# PXO_1_0.net
KiCad netlist of a schematic drawn in EAGLE
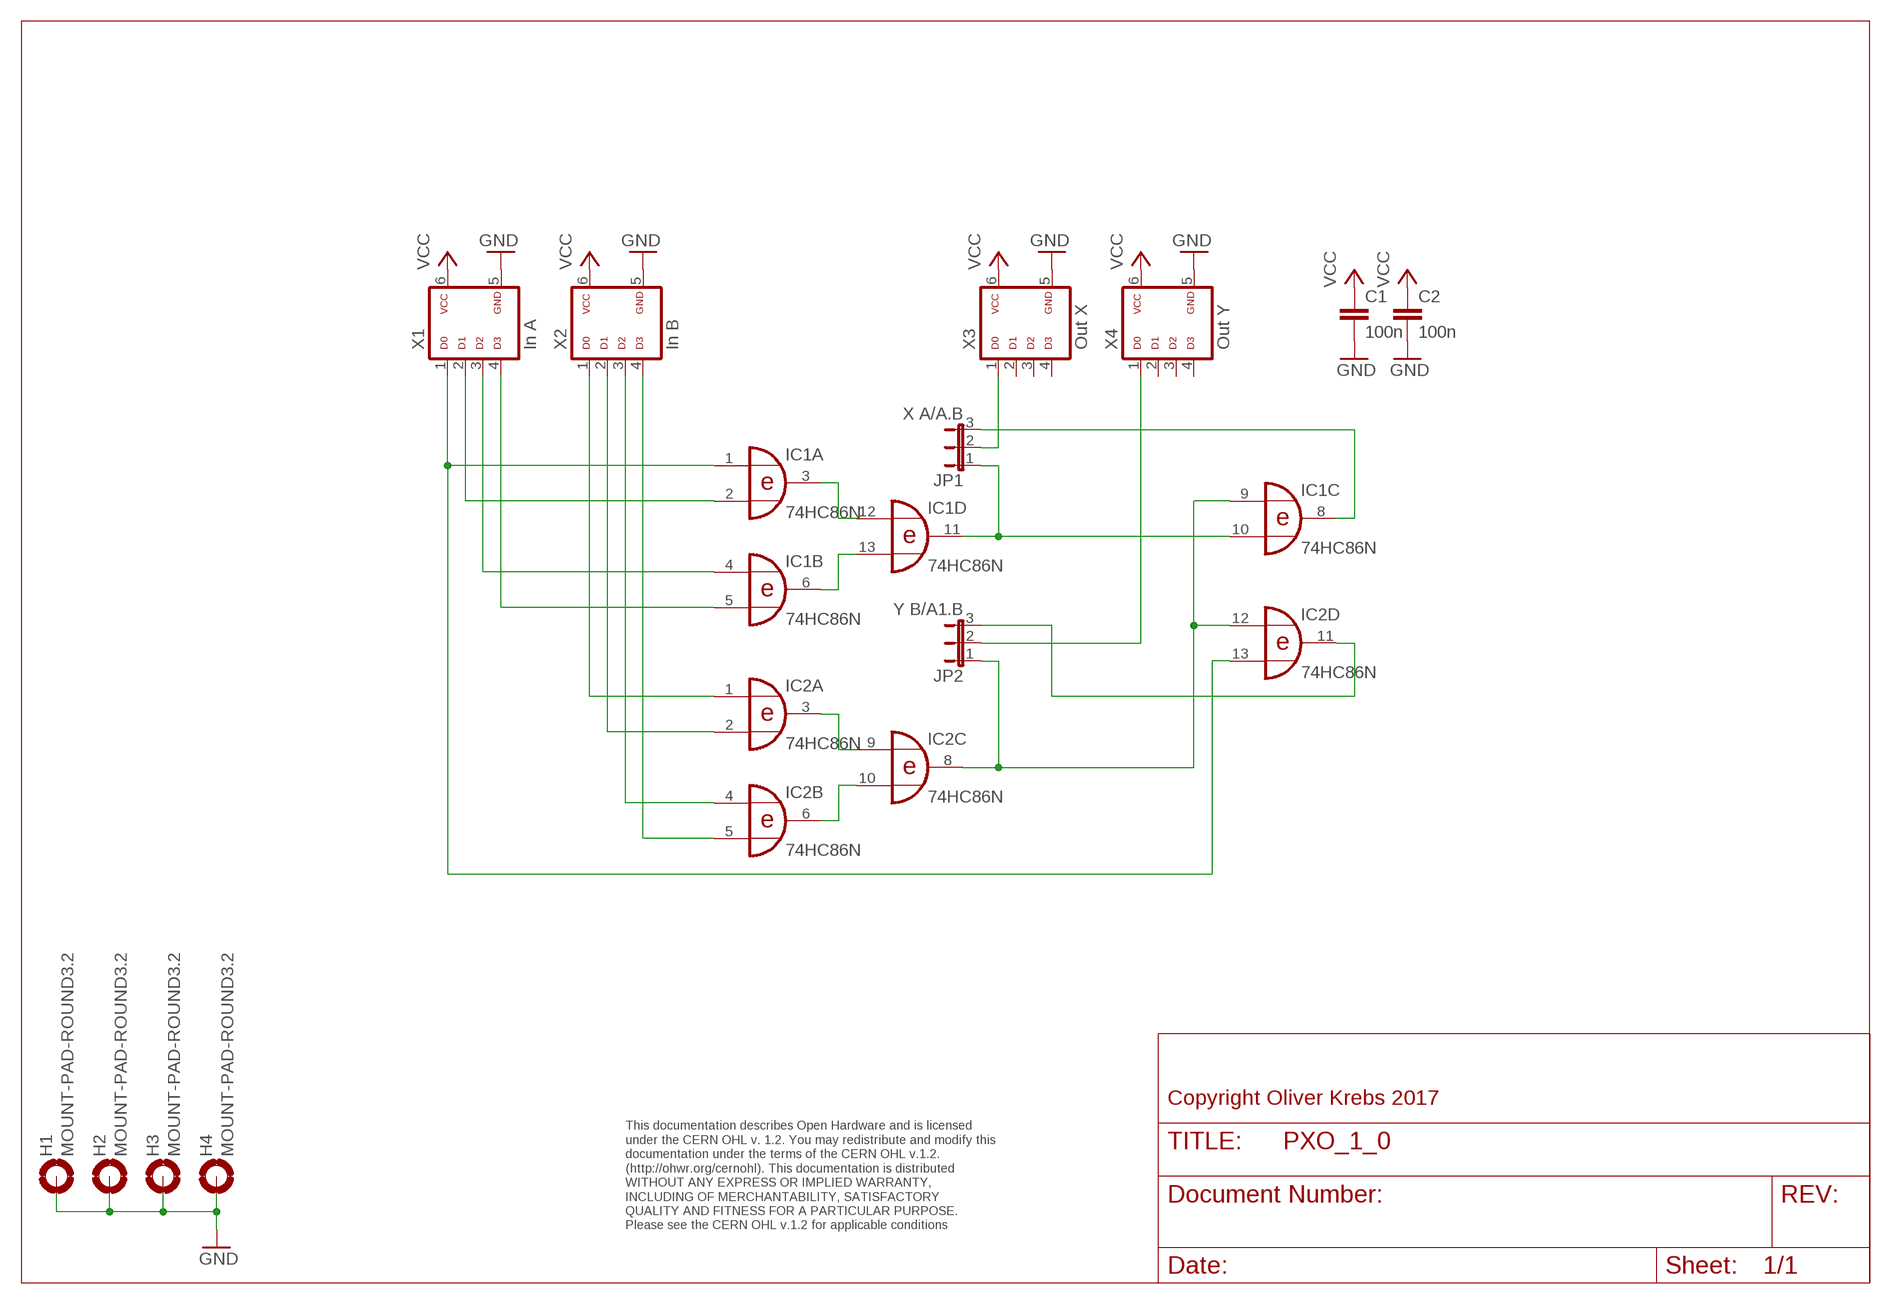
[diagram p0: schematic, sheet 1]

(export (version "E")
  (design (tool "Eeschema 10.0.6"))
  (components
    (comp (ref "C1")
      (value "100n")
      (footprint "eagle-import:C050-025X075")
      (libsource (lib "eagle-import") (part "C-EU050-025X075"))
    )
    (comp (ref "C2")
      (value "100n")
      (footprint "eagle-import:C050-025X075")
      (libsource (lib "eagle-import") (part "C-EU050-025X075"))
    )
    (comp (ref "H1")
      (value "MOUNT-PAD-ROUND3.2")
      (footprint "eagle-import:3,2-PAD")
      (libsource (lib "eagle-import") (part "MOUNT-PAD-ROUND3.2"))
    )
    (comp (ref "H2")
      (value "MOUNT-PAD-ROUND3.2")
      (footprint "eagle-import:3,2-PAD")
      (libsource (lib "eagle-import") (part "MOUNT-PAD-ROUND3.2"))
    )
    (comp (ref "H3")
      (value "MOUNT-PAD-ROUND3.2")
      (footprint "eagle-import:3,2-PAD")
      (libsource (lib "eagle-import") (part "MOUNT-PAD-ROUND3.2"))
    )
    (comp (ref "H4")
      (value "MOUNT-PAD-ROUND3.2")
      (footprint "eagle-import:3,2-PAD")
      (libsource (lib "eagle-import") (part "MOUNT-PAD-ROUND3.2"))
    )
    (comp (ref "IC1")
      (value "74HC86N")
      (footprint "eagle-import:DIL14")
      (libsource (lib "eagle-import") (part "7486NHC"))
    )
    (comp (ref "IC2")
      (value "74HC86N")
      (footprint "eagle-import:DIL14")
      (libsource (lib "eagle-import") (part "7486NHC"))
    )
    (comp (ref "JP1")
      (value "X A/A.B")
      (footprint "eagle-import:JP2-U")
      (libsource (lib "eagle-import") (part "JP2EJP2-U"))
    )
    (comp (ref "JP2")
      (value "Y B/A1.B")
      (footprint "eagle-import:JP2-U")
      (libsource (lib "eagle-import") (part "JP2EJP2-U"))
    )
    (comp (ref "X1")
      (value "In A")
      (footprint "eagle-import:ML-6")
      (libsource (lib "eagle-import") (part "ML6D"))
    )
    (comp (ref "X2")
      (value "In B")
      (footprint "eagle-import:ML-6")
      (libsource (lib "eagle-import") (part "ML6D"))
    )
    (comp (ref "X3")
      (value "Out X")
      (footprint "eagle-import:ML-6")
      (libsource (lib "eagle-import") (part "ML6D"))
    )
    (comp (ref "X4")
      (value "Out Y")
      (footprint "eagle-import:ML-6")
      (libsource (lib "eagle-import") (part "ML6D"))
    )
  )
  (nets
    (net (code "1") (name "GND") (class "Default")
      (node (ref "C1") (pin "2") (pinfunction "2_2") (pintype "passive"))
      (node (ref "C2") (pin "2") (pinfunction "2_2") (pintype "passive"))
      (node (ref "H1") (pin "B3,2") (pinfunction "MOUNT_B3,2") (pintype "passive"))
      (node (ref "H2") (pin "B3,2") (pinfunction "MOUNT_B3,2") (pintype "passive"))
      (node (ref "H3") (pin "B3,2") (pinfunction "MOUNT_B3,2") (pintype "passive"))
      (node (ref "H4") (pin "B3,2") (pinfunction "MOUNT_B3,2") (pintype "passive"))
      (node (ref "X1") (pin "5") (pinfunction "5_5") (pintype "passive"))
      (node (ref "X2") (pin "5") (pinfunction "5_5") (pintype "passive"))
      (node (ref "X3") (pin "5") (pinfunction "5_5") (pintype "passive"))
      (node (ref "X4") (pin "5") (pinfunction "5_5") (pintype "passive"))
    )
    (net (code "2") (name "Net-(IC1A-I0)") (class "Default")
      (node (ref "IC1") (pin "1") (pinfunction "I0_1") (pintype "input"))
      (node (ref "IC2") (pin "13") (pinfunction "I1_13") (pintype "input"))
      (node (ref "X1") (pin "1") (pinfunction "1_1") (pintype "passive"))
    )
    (net (code "3") (name "Net-(IC1A-I1)") (class "Default")
      (node (ref "IC1") (pin "2") (pinfunction "I1_2") (pintype "input"))
      (node (ref "X1") (pin "2") (pinfunction "2_2") (pintype "passive"))
    )
    (net (code "4") (name "Net-(IC1A-O)") (class "Default")
      (node (ref "IC1") (pin "12") (pinfunction "I0_12") (pintype "input"))
      (node (ref "IC1") (pin "3") (pinfunction "O_3") (pintype "output"))
    )
    (net (code "5") (name "Net-(IC1B-I0)") (class "Default")
      (node (ref "IC1") (pin "4") (pinfunction "I0_4") (pintype "input"))
      (node (ref "X1") (pin "3") (pinfunction "3_3") (pintype "passive"))
    )
    (net (code "6") (name "Net-(IC1B-I1)") (class "Default")
      (node (ref "IC1") (pin "5") (pinfunction "I1_5") (pintype "input"))
      (node (ref "X1") (pin "4") (pinfunction "4_4") (pintype "passive"))
    )
    (net (code "7") (name "Net-(IC1B-O)") (class "Default")
      (node (ref "IC1") (pin "13") (pinfunction "I1_13") (pintype "input"))
      (node (ref "IC1") (pin "6") (pinfunction "O_6") (pintype "output"))
    )
    (net (code "8") (name "Net-(IC1C-I0)") (class "Default")
      (node (ref "IC1") (pin "9") (pinfunction "I0_9") (pintype "input"))
      (node (ref "IC2") (pin "12") (pinfunction "I0_12") (pintype "input"))
      (node (ref "IC2") (pin "8") (pinfunction "O_8") (pintype "output"))
      (node (ref "JP2") (pin "1") (pinfunction "1_1") (pintype "passive"))
    )
    (net (code "9") (name "Net-(IC1C-I1)") (class "Default")
      (node (ref "IC1") (pin "10") (pinfunction "I1_10") (pintype "input"))
      (node (ref "IC1") (pin "11") (pinfunction "O_11") (pintype "output"))
      (node (ref "JP1") (pin "1") (pinfunction "1_1") (pintype "passive"))
    )
    (net (code "10") (name "Net-(IC1C-O)") (class "Default")
      (node (ref "IC1") (pin "8") (pinfunction "O_8") (pintype "output"))
      (node (ref "JP1") (pin "3") (pinfunction "3_3") (pintype "passive"))
    )
    (net (code "11") (name "Net-(IC2A-I0)") (class "Default")
      (node (ref "IC2") (pin "1") (pinfunction "I0_1") (pintype "input"))
      (node (ref "X2") (pin "1") (pinfunction "1_1") (pintype "passive"))
    )
    (net (code "12") (name "Net-(IC2A-I1)") (class "Default")
      (node (ref "IC2") (pin "2") (pinfunction "I1_2") (pintype "input"))
      (node (ref "X2") (pin "2") (pinfunction "2_2") (pintype "passive"))
    )
    (net (code "13") (name "Net-(IC2A-O)") (class "Default")
      (node (ref "IC2") (pin "3") (pinfunction "O_3") (pintype "output"))
      (node (ref "IC2") (pin "9") (pinfunction "I0_9") (pintype "input"))
    )
    (net (code "14") (name "Net-(IC2B-I0)") (class "Default")
      (node (ref "IC2") (pin "4") (pinfunction "I0_4") (pintype "input"))
      (node (ref "X2") (pin "3") (pinfunction "3_3") (pintype "passive"))
    )
    (net (code "15") (name "Net-(IC2B-I1)") (class "Default")
      (node (ref "IC2") (pin "5") (pinfunction "I1_5") (pintype "input"))
      (node (ref "X2") (pin "4") (pinfunction "4_4") (pintype "passive"))
    )
    (net (code "16") (name "Net-(IC2B-O)") (class "Default")
      (node (ref "IC2") (pin "10") (pinfunction "I1_10") (pintype "input"))
      (node (ref "IC2") (pin "6") (pinfunction "O_6") (pintype "output"))
    )
    (net (code "17") (name "Net-(IC2D-O)") (class "Default")
      (node (ref "IC2") (pin "11") (pinfunction "O_11") (pintype "output"))
      (node (ref "JP2") (pin "3") (pinfunction "3_3") (pintype "passive"))
    )
    (net (code "18") (name "Net-(JP1-Pad2)") (class "Default")
      (node (ref "JP1") (pin "2") (pinfunction "2_2") (pintype "passive"))
      (node (ref "X3") (pin "1") (pinfunction "1_1") (pintype "passive"))
    )
    (net (code "19") (name "Net-(JP2-Pad2)") (class "Default")
      (node (ref "JP2") (pin "2") (pinfunction "2_2") (pintype "passive"))
      (node (ref "X4") (pin "1") (pinfunction "1_1") (pintype "passive"))
    )
    (net (code "20") (name "VCC") (class "Default")
      (node (ref "C1") (pin "1") (pinfunction "1_1") (pintype "passive"))
      (node (ref "C2") (pin "1") (pinfunction "1_1") (pintype "passive"))
      (node (ref "X1") (pin "6") (pinfunction "6_6") (pintype "passive"))
      (node (ref "X2") (pin "6") (pinfunction "6_6") (pintype "passive"))
      (node (ref "X3") (pin "6") (pinfunction "6_6") (pintype "passive"))
      (node (ref "X4") (pin "6") (pinfunction "6_6") (pintype "passive"))
    )
    (net (code "21") (name "unconnected-(X3-Pad2)") (class "Default")
      (node (ref "X3") (pin "2") (pinfunction "2_2") (pintype "passive"))
    )
    (net (code "22") (name "unconnected-(X3-Pad3)") (class "Default")
      (node (ref "X3") (pin "3") (pinfunction "3_3") (pintype "passive"))
    )
    (net (code "23") (name "unconnected-(X3-Pad4)") (class "Default")
      (node (ref "X3") (pin "4") (pinfunction "4_4") (pintype "passive"))
    )
    (net (code "24") (name "unconnected-(X4-Pad2)") (class "Default")
      (node (ref "X4") (pin "2") (pinfunction "2_2") (pintype "passive"))
    )
    (net (code "25") (name "unconnected-(X4-Pad3)") (class "Default")
      (node (ref "X4") (pin "3") (pinfunction "3_3") (pintype "passive"))
    )
    (net (code "26") (name "unconnected-(X4-Pad4)") (class "Default")
      (node (ref "X4") (pin "4") (pinfunction "4_4") (pintype "passive"))
    )
  )
)
